# node.net
KiCad netlist of a schematic drawn in EAGLE
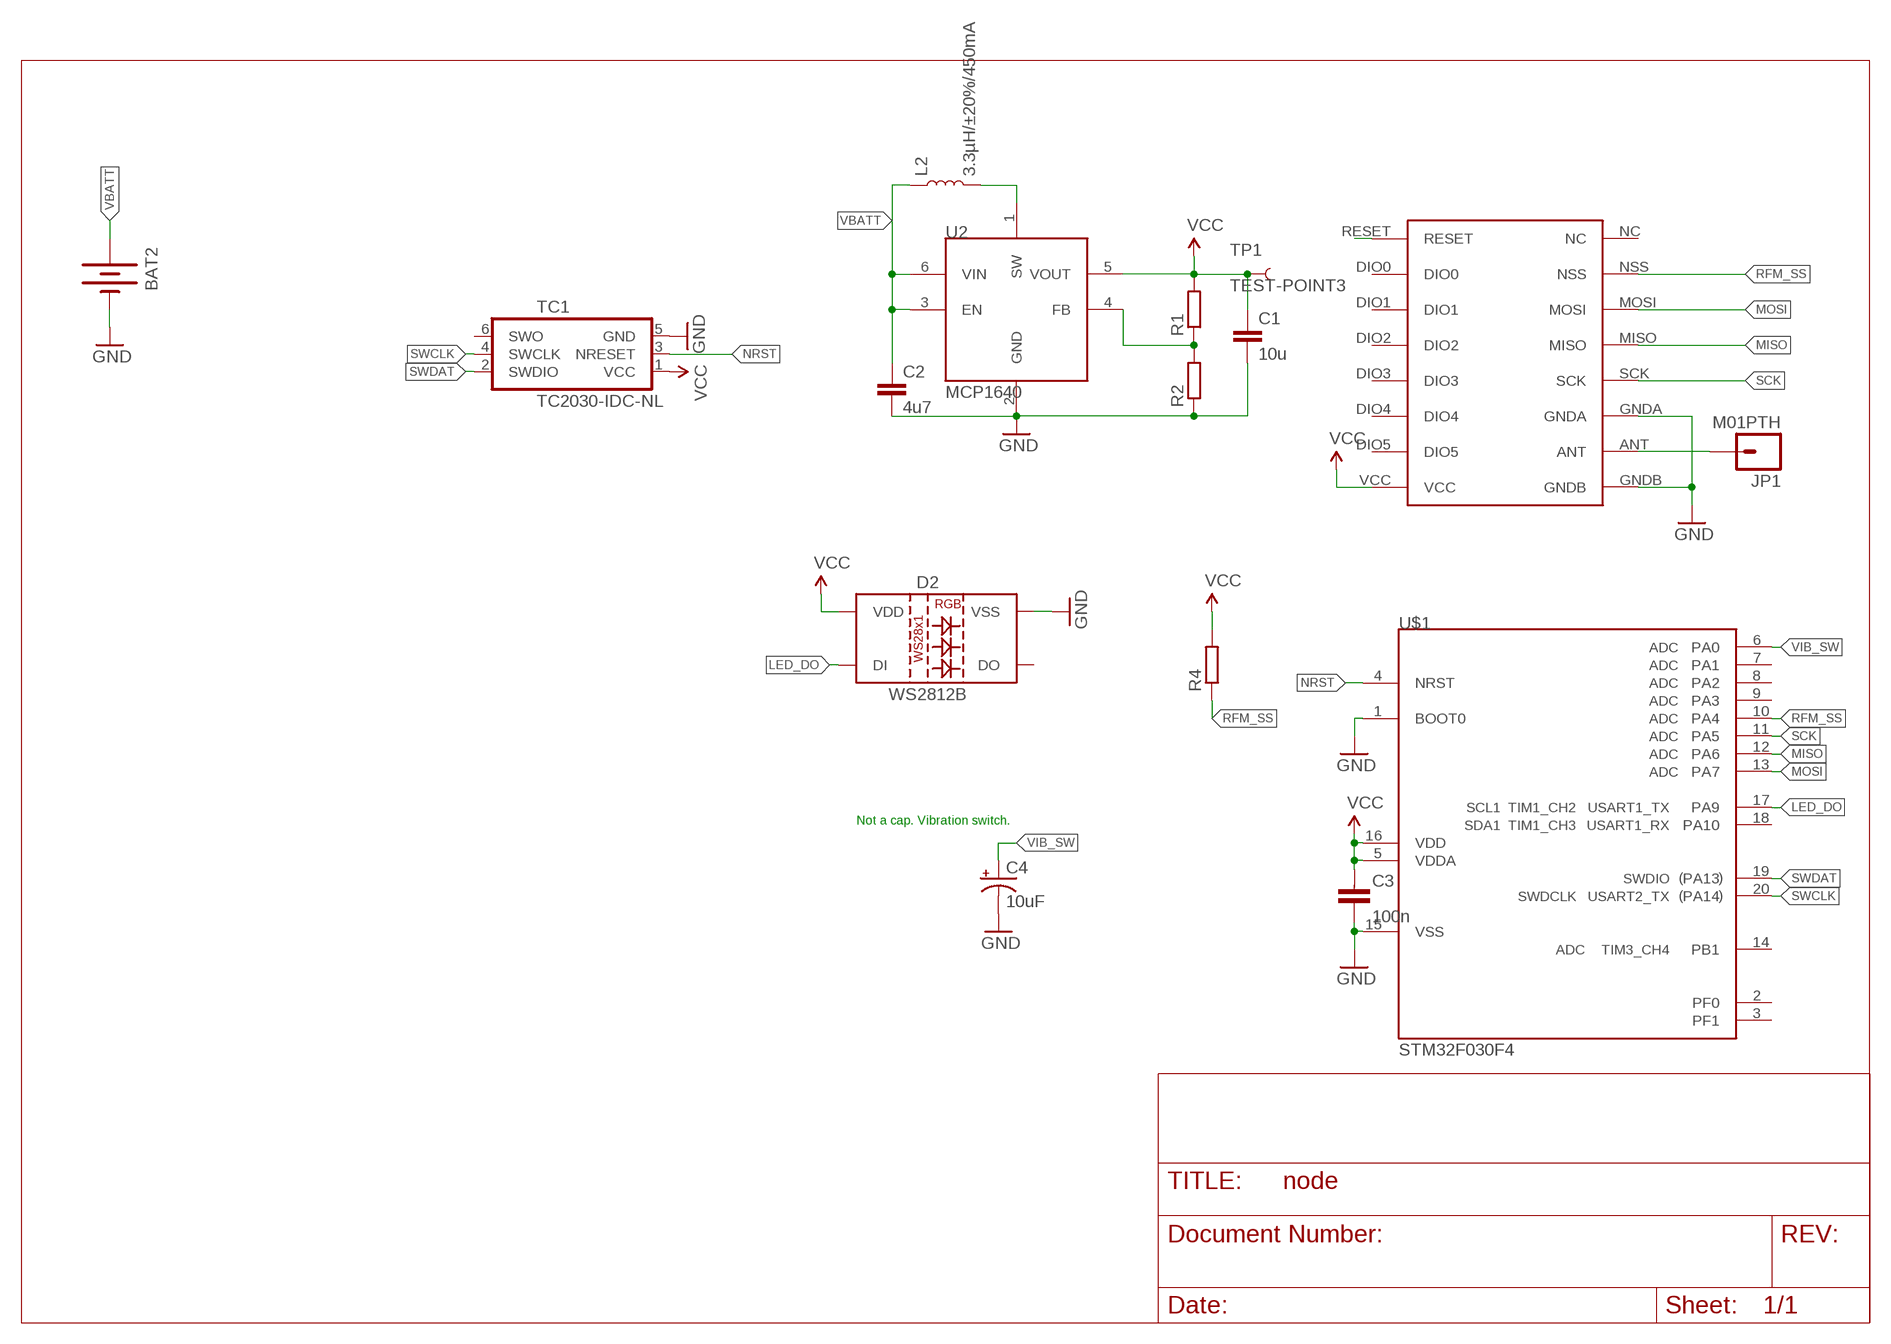
[diagram p0: schematic, sheet 1]

(export (version "E")
  (design (tool "Eeschema 10.0.6"))
  (components
    (comp (ref "BAT2")
      (value "BATTERYAA")
      (footprint "eagle-import:BATTERY-AA")
      (libsource (lib "eagle-import") (part "BATTERYAA"))
    )
    (comp (ref "C1")
      (value "10u")
      (footprint "eagle-import:C0603")
      (libsource (lib "eagle-import") (part "C-EUC0603"))
    )
    (comp (ref "C2")
      (value "4u7")
      (footprint "eagle-import:C0603")
      (libsource (lib "eagle-import") (part "C-EUC0603"))
    )
    (comp (ref "C3")
      (value "100n")
      (footprint "eagle-import:C0603-N")
      (libsource (lib "eagle-import") (part "CAPACITOR0603-N"))
    )
    (comp (ref "C4")
      (value "10uF")
      (footprint "eagle-import:CPOL-RADIAL-2.5MM-5MM")
      (libsource (lib "eagle-import") (part "10UF-POLAR-RADIAL-2.5MM-25V-20%"))
    )
    (comp (ref "D2")
      (value "WS2812B")
      (footprint "eagle-import:WS2812B")
      (libsource (lib "eagle-import") (part "WS2812B"))
    )
    (comp (ref "JP1")
      (value "M01PTH")
      (footprint "eagle-import:1X01")
      (libsource (lib "eagle-import") (part "M01PTH"))
    )
    (comp (ref "L2")
      (value "3.3µH/±20%/450mA")
      (footprint "eagle-import:0805")
      (libsource (lib "eagle-import") (part "INDUCTOR-0805-3.3UH"))
    )
    (comp (ref "R1")
      (value "R-EU_R0603")
      (footprint "eagle-import:R0603")
      (libsource (lib "eagle-import") (part "R-EU_R0603"))
    )
    (comp (ref "R2")
      (value "R-EU_R0603")
      (footprint "eagle-import:R0603")
      (libsource (lib "eagle-import") (part "R-EU_R0603"))
    )
    (comp (ref "R4")
      (value "R-EU_R0603")
      (footprint "eagle-import:R0603")
      (libsource (lib "eagle-import") (part "R-EU_R0603"))
    )
    (comp (ref "TC1")
      (value "TC2030-IDC-NL")
      (footprint "eagle-import:TC2030-IDC-NL")
      (libsource (lib "eagle-import") (part "TC2030-IDC-NL"))
    )
    (comp (ref "TP1")
      (value "TEST-POINT3")
      (footprint "eagle-import:PAD.03X.03")
      (libsource (lib "eagle-import") (part "TEST-POINT3"))
    )
    (comp (ref "U$1")
      (value "STM32F030F4")
      (footprint "eagle-import:TSSOP20")
      (libsource (lib "eagle-import") (part "STM32F030F4"))
    )
    (comp (ref "U$4")
      (value "RFM69HW")
      (footprint "eagle-import:RFM")
      (libsource (lib "eagle-import") (part "RFM69HW"))
    )
    (comp (ref "U2")
      (value "MCP1640")
      (footprint "eagle-import:SOT23-6")
      (libsource (lib "eagle-import") (part "MCP1640"))
    )
  )
  (nets
    (net (code "1") (name "GND") (class "Default")
      (node (ref "BAT2") (pin "GND@1") (pinfunction "-_GND@1") (pintype "power_in"))
      (node (ref "C1") (pin "2") (pinfunction "2_2") (pintype "passive"))
      (node (ref "C2") (pin "2") (pinfunction "2_2") (pintype "passive"))
      (node (ref "C3") (pin "2") (pinfunction "2_2") (pintype "passive"))
      (node (ref "C4") (pin "2") (pinfunction "-_2") (pintype "passive"))
      (node (ref "D2") (pin "3") (pinfunction "VSS_3") (pintype "bidirectional"))
      (node (ref "R2") (pin "1") (pinfunction "1_1") (pintype "passive"))
      (node (ref "TC1") (pin "5") (pinfunction "GND_5") (pintype "passive"))
      (node (ref "U$1") (pin "1") (pinfunction "BOOT0_1") (pintype "input"))
      (node (ref "U$1") (pin "15") (pinfunction "VSS_15") (pintype "power_in"))
      (node (ref "U$4") (pin "GNDA") (pinfunction "GNDA_GNDA") (pintype "bidirectional"))
      (node (ref "U$4") (pin "GNDB") (pinfunction "GNDB_GNDB") (pintype "bidirectional"))
      (node (ref "U2") (pin "2") (pinfunction "GND_2") (pintype "power_in"))
    )
    (net (code "2") (name "LED_DO") (class "Default")
      (node (ref "D2") (pin "4") (pinfunction "DI_4") (pintype "bidirectional"))
      (node (ref "U$1") (pin "17") (pinfunction "PA9_17") (pintype "bidirectional"))
    )
    (net (code "3") (name "MISO") (class "Default")
      (node (ref "U$1") (pin "12") (pinfunction "PA6_12") (pintype "bidirectional"))
      (node (ref "U$4") (pin "MISO") (pinfunction "MISO_MISO") (pintype "bidirectional"))
    )
    (net (code "4") (name "MOSI") (class "Default")
      (node (ref "U$1") (pin "13") (pinfunction "PA7_13") (pintype "bidirectional"))
      (node (ref "U$4") (pin "MOSI") (pinfunction "MOSI_MOSI") (pintype "bidirectional"))
    )
    (net (code "5") (name "NRST") (class "Default")
      (node (ref "TC1") (pin "3") (pinfunction "NRESET_3") (pintype "passive"))
      (node (ref "U$1") (pin "4") (pinfunction "NRST_4") (pintype "input"))
    )
    (net (code "6") (name "Net-(JP1-Pad1)") (class "Default")
      (node (ref "JP1") (pin "1") (pinfunction "1_1") (pintype "passive"))
      (node (ref "U$4") (pin "ANT") (pinfunction "ANT_ANT") (pintype "bidirectional"))
    )
    (net (code "7") (name "Net-(U2-FB)") (class "Default")
      (node (ref "R1") (pin "1") (pinfunction "1_1") (pintype "passive"))
      (node (ref "R2") (pin "2") (pinfunction "2_2") (pintype "passive"))
      (node (ref "U2") (pin "4") (pinfunction "FB_4") (pintype "input"))
    )
    (net (code "8") (name "Net-(U2-SW)") (class "Default")
      (node (ref "L2") (pin "2") (pinfunction "2_2") (pintype "passive"))
      (node (ref "U2") (pin "1") (pinfunction "SW_1") (pintype "input"))
    )
    (net (code "9") (name "RFM_SS") (class "Default")
      (node (ref "R4") (pin "1") (pinfunction "1_1") (pintype "passive"))
      (node (ref "U$1") (pin "10") (pinfunction "PA4_10") (pintype "bidirectional"))
      (node (ref "U$4") (pin "NSS") (pinfunction "NSS_NSS") (pintype "bidirectional"))
    )
    (net (code "10") (name "SCK") (class "Default")
      (node (ref "U$1") (pin "11") (pinfunction "PA5_11") (pintype "bidirectional"))
      (node (ref "U$4") (pin "SCK") (pinfunction "SCK_SCK") (pintype "bidirectional"))
    )
    (net (code "11") (name "SWCLK") (class "Default")
      (node (ref "TC1") (pin "4") (pinfunction "SWCLK_4") (pintype "passive"))
      (node (ref "U$1") (pin "20") (pinfunction "PA14_20") (pintype "bidirectional"))
    )
    (net (code "12") (name "SWDAT") (class "Default")
      (node (ref "TC1") (pin "2") (pinfunction "SWDIO_2") (pintype "passive"))
      (node (ref "U$1") (pin "19") (pinfunction "PA13_19") (pintype "bidirectional"))
    )
    (net (code "13") (name "VBATT") (class "Default")
      (node (ref "BAT2") (pin "PWR@1") (pinfunction "+_PWR@1") (pintype "power_in"))
      (node (ref "C2") (pin "1") (pinfunction "1_1") (pintype "passive"))
      (node (ref "L2") (pin "1") (pinfunction "1_1") (pintype "passive"))
      (node (ref "U2") (pin "3") (pinfunction "EN_3") (pintype "input"))
      (node (ref "U2") (pin "6") (pinfunction "VIN_6") (pintype "power_in"))
    )
    (net (code "14") (name "VCC") (class "Default")
      (node (ref "C1") (pin "1") (pinfunction "1_1") (pintype "passive"))
      (node (ref "C3") (pin "1") (pinfunction "1_1") (pintype "passive"))
      (node (ref "D2") (pin "1") (pinfunction "VDD_1") (pintype "bidirectional"))
      (node (ref "R1") (pin "2") (pinfunction "2_2") (pintype "passive"))
      (node (ref "R4") (pin "2") (pinfunction "2_2") (pintype "passive"))
      (node (ref "TC1") (pin "1") (pinfunction "VCC_1") (pintype "passive"))
      (node (ref "TP1") (pin "P$1") (pinfunction "1_P$1") (pintype "bidirectional"))
      (node (ref "U$1") (pin "16") (pinfunction "VDD_16") (pintype "power_in"))
      (node (ref "U$1") (pin "5") (pinfunction "VDDA_5") (pintype "power_in"))
      (node (ref "U$4") (pin "VCC") (pinfunction "VCC_VCC") (pintype "bidirectional"))
      (node (ref "U2") (pin "5") (pinfunction "VOUT_5") (pintype "output"))
    )
    (net (code "15") (name "VIB_SW") (class "Default")
      (node (ref "C4") (pin "1") (pinfunction "+_1") (pintype "passive"))
      (node (ref "U$1") (pin "6") (pinfunction "PA0_6") (pintype "bidirectional"))
    )
    (net (code "16") (name "unconnected-(D2-DO-Pad2)") (class "Default")
      (node (ref "D2") (pin "2") (pinfunction "DO_2") (pintype "bidirectional"))
    )
    (net (code "17") (name "unconnected-(TC1-SWO-Pad6)") (class "Default")
      (node (ref "TC1") (pin "6") (pinfunction "SWO_6") (pintype "passive"))
    )
    (net (code "18") (name "unconnected-(U$1-PA1-Pad7)") (class "Default")
      (node (ref "U$1") (pin "7") (pinfunction "PA1_7") (pintype "bidirectional"))
    )
    (net (code "19") (name "unconnected-(U$1-PA2-Pad8)") (class "Default")
      (node (ref "U$1") (pin "8") (pinfunction "PA2_8") (pintype "bidirectional"))
    )
    (net (code "20") (name "unconnected-(U$1-PA3-Pad9)") (class "Default")
      (node (ref "U$1") (pin "9") (pinfunction "PA3_9") (pintype "bidirectional"))
    )
    (net (code "21") (name "unconnected-(U$1-PA10-Pad18)") (class "Default")
      (node (ref "U$1") (pin "18") (pinfunction "PA10_18") (pintype "bidirectional"))
    )
    (net (code "22") (name "unconnected-(U$1-PB1-Pad14)") (class "Default")
      (node (ref "U$1") (pin "14") (pinfunction "PB1_14") (pintype "bidirectional"))
    )
    (net (code "23") (name "unconnected-(U$1-PF0-Pad2)") (class "Default")
      (node (ref "U$1") (pin "2") (pinfunction "PF0_2") (pintype "bidirectional"))
    )
    (net (code "24") (name "unconnected-(U$1-PF1-Pad3)") (class "Default")
      (node (ref "U$1") (pin "3") (pinfunction "PF1_3") (pintype "bidirectional"))
    )
    (net (code "25") (name "unconnected-(U$4-PadDIO0)") (class "Default")
      (node (ref "U$4") (pin "DIO0") (pinfunction "DIO0_DIO0") (pintype "bidirectional"))
    )
    (net (code "26") (name "unconnected-(U$4-PadDIO1)") (class "Default")
      (node (ref "U$4") (pin "DIO1") (pinfunction "DIO1_DIO1") (pintype "bidirectional"))
    )
    (net (code "27") (name "unconnected-(U$4-PadDIO2)") (class "Default")
      (node (ref "U$4") (pin "DIO2") (pinfunction "DIO2_DIO2") (pintype "bidirectional"))
    )
    (net (code "28") (name "unconnected-(U$4-PadDIO3)") (class "Default")
      (node (ref "U$4") (pin "DIO3") (pinfunction "DIO3_DIO3") (pintype "bidirectional"))
    )
    (net (code "29") (name "unconnected-(U$4-PadDIO4)") (class "Default")
      (node (ref "U$4") (pin "DIO4") (pinfunction "DIO4_DIO4") (pintype "bidirectional"))
    )
    (net (code "30") (name "unconnected-(U$4-PadDIO5)") (class "Default")
      (node (ref "U$4") (pin "DIO5") (pinfunction "DIO5_DIO5") (pintype "bidirectional"))
    )
    (net (code "31") (name "unconnected-(U$4-PadNC)") (class "Default")
      (node (ref "U$4") (pin "NC") (pinfunction "NC_NC") (pintype "bidirectional"))
    )
    (net (code "32") (name "unconnected-(U$4-PadRESET)") (class "Default")
      (node (ref "U$4") (pin "RESET") (pinfunction "RESET_RESET") (pintype "bidirectional"))
    )
  )
)
